# RF-Pi_Carrier_Board_v1.net
KiCad netlist of a schematic drawn in Altium Designer
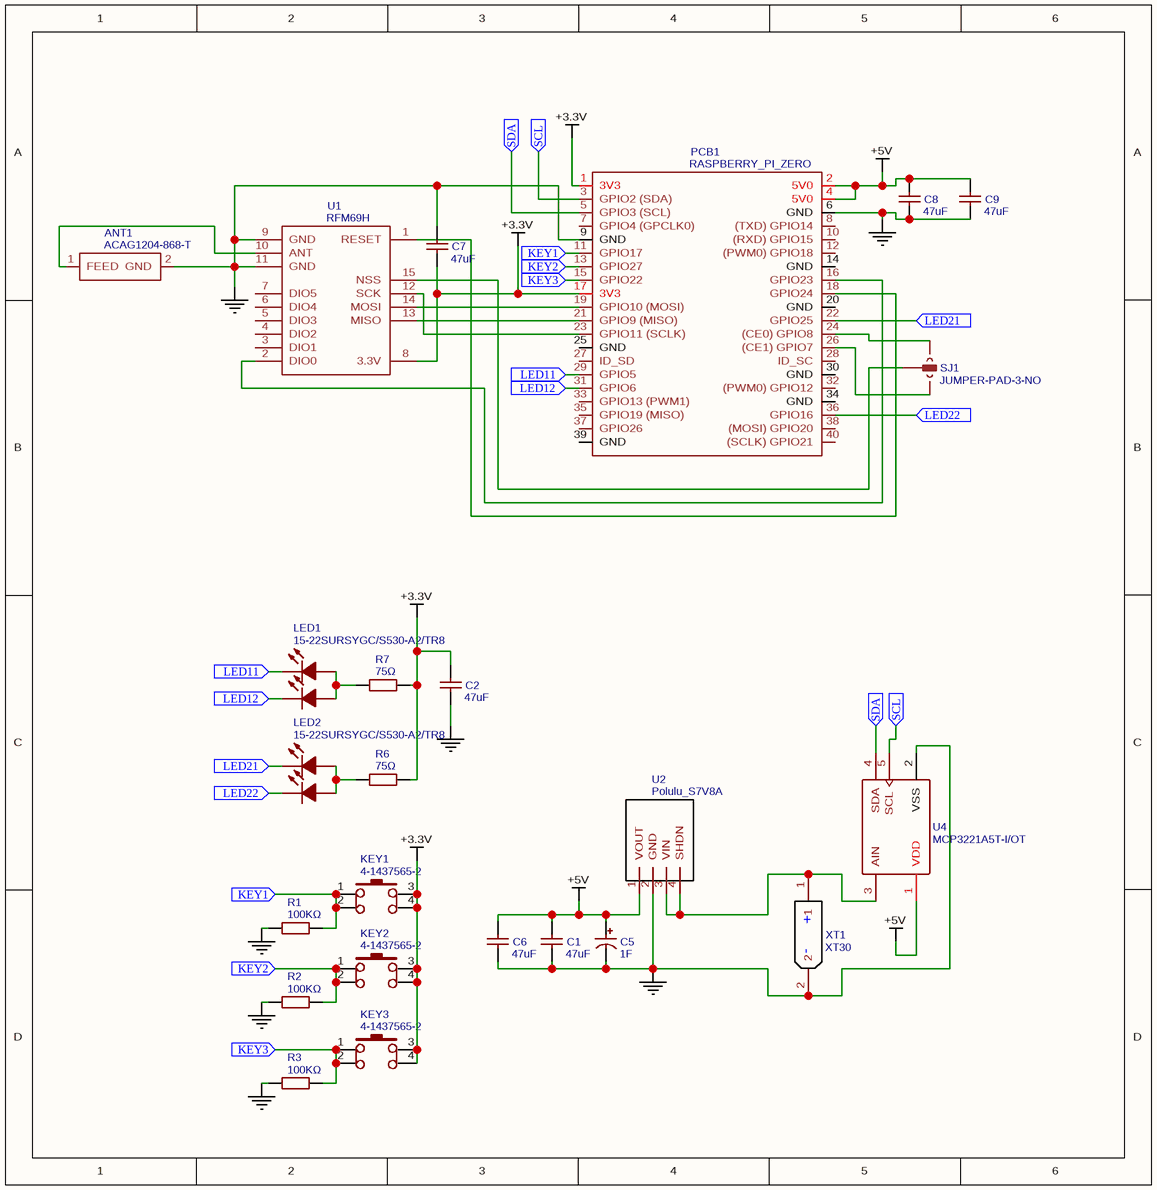
[diagram p0: RF-Pi+Carrier+Board+v1.schdoc]

(export (version "E")
  (design (tool "Eeschema 10.0.6"))
  (components
    (comp (ref "ANT1")
      (value "ACAG1204-868-T")
      (description "868 Ceramic Chip Antenna")
      (fields (field (name "CONTRIBUTOR") "JUehV"))
      (libsource (lib "altium-import") (part "root_0_ACAG1204-868-T_"))
    )
    (comp (ref "C1")
      (value "47uF")
      (fields
        (field (name "BOM_MANUFACTURER PART") "1206F476M100NT")
        (field (name "BOM_SUPPLIER PART") "C30349")
      )
      (libsource (lib "altium-import") (part "root_1_47uF_"))
    )
    (comp (ref "C2")
      (value "47uF")
      (fields
        (field (name "BOM_MANUFACTURER PART") "1206F476M100NT")
        (field (name "BOM_SUPPLIER PART") "C30349")
      )
      (libsource (lib "altium-import") (part "root_1_47uF_"))
    )
    (comp (ref "C5")
      (value "1F")
      (fields
        (field (name "BOM_MANUFACTURER PART") "SE-5R5-D105VYH")
        (field (name "BOM_SUPPLIER PART") "C118887")
        (field (name "CONTRIBUTOR") "LCSC")
      )
      (libsource (lib "altium-import") (part "root_3_1F_"))
    )
    (comp (ref "C6")
      (value "47uF")
      (fields
        (field (name "BOM_MANUFACTURER PART") "1206F476M100NT")
        (field (name "BOM_SUPPLIER PART") "C30349")
      )
      (libsource (lib "altium-import") (part "root_1_47uF_"))
    )
    (comp (ref "C7")
      (value "47uF")
      (fields
        (field (name "BOM_MANUFACTURER PART") "1206F476M100NT")
        (field (name "BOM_SUPPLIER PART") "C30349")
      )
      (libsource (lib "altium-import") (part "root_1_47uF_"))
    )
    (comp (ref "C8")
      (value "47uF")
      (fields
        (field (name "BOM_MANUFACTURER PART") "1206F476M100NT")
        (field (name "BOM_SUPPLIER PART") "C30349")
      )
      (libsource (lib "altium-import") (part "root_1_47uF_"))
    )
    (comp (ref "C9")
      (value "47uF")
      (fields
        (field (name "BOM_MANUFACTURER PART") "1206F476M100NT")
        (field (name "BOM_SUPPLIER PART") "C30349")
      )
      (libsource (lib "altium-import") (part "root_1_47uF_"))
    )
    (comp (ref "KEY1")
      (value "4-1437565-2")
      (fields (field (name "BOM_SUPPLIER PART") "C86487"))
      (libsource (lib "altium-import") (part "root_0_4-1437565-2_"))
    )
    (comp (ref "KEY2")
      (value "4-1437565-2")
      (fields (field (name "BOM_SUPPLIER PART") "C86487"))
      (libsource (lib "altium-import") (part "root_0_4-1437565-2_"))
    )
    (comp (ref "KEY3")
      (value "4-1437565-2")
      (fields (field (name "BOM_SUPPLIER PART") "C86487"))
      (libsource (lib "altium-import") (part "root_0_4-1437565-2_"))
    )
    (comp (ref "LED1")
      (value "15-22SURSYGC/S530-A2/TR8")
      (fields (field (name "BOM_SUPPLIER PART") "C131251") (field (name "CONTRIBUTOR") "LCSC"))
      (libsource (lib "altium-import") (part "root_0_15-22SURSYGC/S530-A2/TR8_"))
    )
    (comp (ref "LED2")
      (value "15-22SURSYGC/S530-A2/TR8")
      (fields (field (name "BOM_SUPPLIER PART") "C131251") (field (name "CONTRIBUTOR") "LCSC"))
      (libsource (lib "altium-import") (part "root_0_15-22SURSYGC/S530-A2/TR8_"))
    )
    (comp (ref "PCB1")
      (value "RASPBERRY_PI_ZERO")
      (description "Raspberry Pi Zero")
      (fields (field (name "BOM_MANUFACTURER PART") "?"))
      (libsource (lib "altium-import") (part "root_0_RASPBERRY_PI_ZERO_"))
    )
    (comp (ref "R1")
      (value "100KΩ")
      (fields
        (field (name "BOM_MANUFACTURER PART") "1206W4J0104T5E")
        (field (name "BOM_SUPPLIER PART") "C25647")
      )
      (libsource (lib "altium-import") (part "root_0_100KΩ_"))
    )
    (comp (ref "R2")
      (value "100KΩ")
      (fields
        (field (name "BOM_MANUFACTURER PART") "1206W4J0104T5E")
        (field (name "BOM_SUPPLIER PART") "C25647")
      )
      (libsource (lib "altium-import") (part "root_0_100KΩ_"))
    )
    (comp (ref "R3")
      (value "100KΩ")
      (fields
        (field (name "BOM_MANUFACTURER PART") "1206W4J0104T5E")
        (field (name "BOM_SUPPLIER PART") "C25647")
      )
      (libsource (lib "altium-import") (part "root_0_100KΩ_"))
    )
    (comp (ref "R6")
      (value "75Ω")
      (fields
        (field (name "BOM_MANUFACTURER PART") "1206W4F750JT5E")
        (field (name "BOM_SUPPLIER PART") "C17987")
      )
      (libsource (lib "altium-import") (part "root_0_75Ω_"))
    )
    (comp (ref "R7")
      (value "75Ω")
      (fields
        (field (name "BOM_MANUFACTURER PART") "1206W4F750JT5E")
        (field (name "BOM_SUPPLIER PART") "C17987")
      )
      (libsource (lib "altium-import") (part "root_0_75Ω_"))
    )
    (comp (ref "SJ1")
      (value "JUMPER-PAD-3-NO")
      (fields (field (name "BOM_MANUFACTURER PART") "?") (field (name "CONTRIBUTOR") "SparkFun"))
      (libsource (lib "altium-import") (part "root_0_JUMPER-PAD-3-NO_"))
    )
    (comp (ref "U1")
      (value "RFM69H")
      (fields
        (field (name "BOM_MANUFACTURER PART") "?")
        (field (name "BOM_SUPPLIER PART") "https://www.pollin.de/p/funkmodul-hoperf-rfm69hcw-868-mhz-tx-rx-810307")
        (field (name "CONTRIBUTOR") "SparkFun")
      )
      (libsource (lib "altium-import") (part "root_2_RFM69H_"))
    )
    (comp (ref "U2")
      (value "Polulu_S7V8A")
      (fields
        (field (name "BOM_MANUFACTURER PART") "?")
        (field (name "BOM_SUPPLIER PART") "2118")
        (field (name "CONTRIBUTOR") "JUehV")
      )
      (libsource (lib "altium-import") (part "root_0_Polulu_S7V8A_"))
    )
    (comp (ref "U4")
      (value "MCP3221A5T-I/OT")
      (fields (field (name "BOM_SUPPLIER PART") "C36310"))
      (libsource (lib "altium-import") (part "root_1_MCP3221A5T-I/OT_"))
    )
    (comp (ref "XT1")
      (value "XT30")
      (fields (field (name "BOM_SUPPLIER PART") "C99101") (field (name "CONTRIBUTOR") "4bucks"))
      (libsource (lib "altium-import") (part "root_3_XT30_"))
    )
  )
  (nets
    (net (code "1") (name "+3.3V") (class "Default")
      (node (ref "C2") (pin "2") (pinfunction "2_2") (pintype "passive"))
      (node (ref "C7") (pin "1") (pinfunction "1_1") (pintype "passive"))
      (node (ref "KEY1") (pin "3") (pinfunction "3_3") (pintype "passive"))
      (node (ref "KEY1") (pin "4") (pinfunction "4_4") (pintype "passive"))
      (node (ref "KEY2") (pin "3") (pinfunction "3_3") (pintype "passive"))
      (node (ref "KEY2") (pin "4") (pinfunction "4_4") (pintype "passive"))
      (node (ref "KEY3") (pin "3") (pinfunction "3_3") (pintype "passive"))
      (node (ref "KEY3") (pin "4") (pinfunction "4_4") (pintype "passive"))
      (node (ref "PCB1") (pin "1") (pinfunction "3V3_1") (pintype "passive"))
      (node (ref "PCB1") (pin "17") (pinfunction "3V3_17") (pintype "passive"))
      (node (ref "R6") (pin "2") (pinfunction "2_2") (pintype "passive"))
      (node (ref "R7") (pin "2") (pinfunction "2_2") (pintype "passive"))
      (node (ref "U1") (pin "8") (pinfunction "3.3V_8") (pintype "passive"))
    )
    (net (code "2") (name "+5V") (class "Default")
      (node (ref "C1") (pin "2") (pinfunction "2_2") (pintype "passive"))
      (node (ref "C5") (pin "1") (pinfunction "1_1") (pintype "passive"))
      (node (ref "C6") (pin "2") (pinfunction "2_2") (pintype "passive"))
      (node (ref "C8") (pin "2") (pinfunction "2_2") (pintype "passive"))
      (node (ref "C9") (pin "2") (pinfunction "2_2") (pintype "passive"))
      (node (ref "PCB1") (pin "2") (pinfunction "5V0_2") (pintype "passive"))
      (node (ref "PCB1") (pin "4") (pinfunction "5V0_4") (pintype "passive"))
      (node (ref "U2") (pin "1") (pinfunction "VOUT_1") (pintype "passive"))
      (node (ref "U4") (pin "1") (pinfunction "VDD_1") (pintype "passive"))
    )
    (net (code "3") (name "/KEY1") (class "Default")
      (node (ref "KEY1") (pin "1") (pinfunction "1_1") (pintype "passive"))
      (node (ref "KEY1") (pin "2") (pinfunction "2_2") (pintype "passive"))
      (node (ref "PCB1") (pin "11") (pinfunction "GPIO17_11") (pintype "passive"))
      (node (ref "R1") (pin "2") (pinfunction "2_2") (pintype "passive"))
    )
    (net (code "4") (name "/KEY2") (class "Default")
      (node (ref "KEY2") (pin "1") (pinfunction "1_1") (pintype "passive"))
      (node (ref "KEY2") (pin "2") (pinfunction "2_2") (pintype "passive"))
      (node (ref "PCB1") (pin "13") (pinfunction "GPIO27_13") (pintype "passive"))
      (node (ref "R2") (pin "2") (pinfunction "2_2") (pintype "passive"))
    )
    (net (code "5") (name "/KEY3") (class "Default")
      (node (ref "KEY3") (pin "1") (pinfunction "1_1") (pintype "passive"))
      (node (ref "KEY3") (pin "2") (pinfunction "2_2") (pintype "passive"))
      (node (ref "PCB1") (pin "15") (pinfunction "GPIO22_15") (pintype "passive"))
      (node (ref "R3") (pin "2") (pinfunction "2_2") (pintype "passive"))
    )
    (net (code "6") (name "/LED11") (class "Default")
      (node (ref "LED1") (pin "2") (pinfunction "K_2") (pintype "passive"))
      (node (ref "PCB1") (pin "29") (pinfunction "GPIO5_29") (pintype "passive"))
    )
    (net (code "7") (name "/LED12") (class "Default")
      (node (ref "LED1") (pin "4") (pinfunction "K_4") (pintype "passive"))
      (node (ref "PCB1") (pin "31") (pinfunction "GPIO6_31") (pintype "passive"))
    )
    (net (code "8") (name "/LED21") (class "Default")
      (node (ref "LED2") (pin "2") (pinfunction "K_2") (pintype "passive"))
      (node (ref "PCB1") (pin "22") (pinfunction "GPIO25_22") (pintype "passive"))
    )
    (net (code "9") (name "/LED22") (class "Default")
      (node (ref "LED2") (pin "4") (pinfunction "K_4") (pintype "passive"))
      (node (ref "PCB1") (pin "36") (pinfunction "GPIO16_36") (pintype "passive"))
    )
    (net (code "10") (name "/SCL") (class "Default")
      (node (ref "PCB1") (pin "3") (pinfunction "GPIO2_(SDA)_3") (pintype "passive"))
      (node (ref "U4") (pin "5") (pinfunction "SCL_5") (pintype "passive"))
    )
    (net (code "11") (name "/SDA") (class "Default")
      (node (ref "PCB1") (pin "5") (pinfunction "GPIO3_(SCL)_5") (pintype "passive"))
      (node (ref "U4") (pin "4") (pinfunction "SDA_4") (pintype "passive"))
    )
    (net (code "12") (name "GND") (class "Default")
      (node (ref "ANT1") (pin "2") (pinfunction "GND_2") (pintype "passive"))
      (node (ref "C1") (pin "1") (pinfunction "1_1") (pintype "passive"))
      (node (ref "C2") (pin "1") (pinfunction "1_1") (pintype "passive"))
      (node (ref "C5") (pin "2") (pinfunction "2_2") (pintype "passive"))
      (node (ref "C6") (pin "1") (pinfunction "1_1") (pintype "passive"))
      (node (ref "C7") (pin "2") (pinfunction "2_2") (pintype "passive"))
      (node (ref "C8") (pin "1") (pinfunction "1_1") (pintype "passive"))
      (node (ref "C9") (pin "1") (pinfunction "1_1") (pintype "passive"))
      (node (ref "PCB1") (pin "6") (pinfunction "GND_6") (pintype "passive"))
      (node (ref "PCB1") (pin "9") (pinfunction "GND_9") (pintype "passive"))
      (node (ref "R1") (pin "1") (pinfunction "1_1") (pintype "passive"))
      (node (ref "R2") (pin "1") (pinfunction "1_1") (pintype "passive"))
      (node (ref "R3") (pin "1") (pinfunction "1_1") (pintype "passive"))
      (node (ref "U1") (pin "11") (pinfunction "GND_11") (pintype "passive"))
      (node (ref "U1") (pin "9") (pinfunction "GND_9") (pintype "passive"))
      (node (ref "U2") (pin "2") (pinfunction "GND_2") (pintype "passive"))
      (node (ref "U4") (pin "2") (pinfunction "VSS_2") (pintype "passive"))
      (node (ref "XT1") (pin "2") (pinfunction "2_2") (pintype "passive"))
    )
    (net (code "13") (name "Net-(ANT1-FEED)") (class "Default")
      (node (ref "ANT1") (pin "1") (pinfunction "FEED_1") (pintype "passive"))
      (node (ref "U1") (pin "10") (pinfunction "ANT_10") (pintype "passive"))
    )
    (net (code "14") (name "Net-(LED1-A-Pad1)") (class "Default")
      (node (ref "LED1") (pin "1") (pinfunction "A_1") (pintype "passive"))
      (node (ref "LED1") (pin "3") (pinfunction "A_3") (pintype "passive"))
      (node (ref "R7") (pin "1") (pinfunction "1_1") (pintype "passive"))
    )
    (net (code "15") (name "Net-(LED2-A-Pad1)") (class "Default")
      (node (ref "LED2") (pin "1") (pinfunction "A_1") (pintype "passive"))
      (node (ref "LED2") (pin "3") (pinfunction "A_3") (pintype "passive"))
      (node (ref "R6") (pin "1") (pinfunction "1_1") (pintype "passive"))
    )
    (net (code "16") (name "Net-(PCB1-(CE0)_GPIO8)") (class "Default")
      (node (ref "PCB1") (pin "24") (pinfunction "(CE0)_GPIO8_24") (pintype "passive"))
      (node (ref "SJ1") (pin "1") (pinfunction "1_1") (pintype "passive"))
    )
    (net (code "17") (name "Net-(PCB1-(CE1)_GPIO7)") (class "Default")
      (node (ref "PCB1") (pin "26") (pinfunction "(CE1)_GPIO7_26") (pintype "passive"))
      (node (ref "SJ1") (pin "3") (pinfunction "3_3") (pintype "passive"))
    )
    (net (code "18") (name "Net-(PCB1-GPIO9_(MISO))") (class "Default")
      (node (ref "PCB1") (pin "21") (pinfunction "GPIO9_(MISO)_21") (pintype "passive"))
      (node (ref "U1") (pin "13") (pinfunction "MISO_13") (pintype "passive"))
    )
    (net (code "19") (name "Net-(PCB1-GPIO10_(MOSI))") (class "Default")
      (node (ref "PCB1") (pin "19") (pinfunction "GPIO10_(MOSI)_19") (pintype "passive"))
      (node (ref "U1") (pin "14") (pinfunction "MOSI_14") (pintype "passive"))
    )
    (net (code "20") (name "Net-(PCB1-GPIO11_(SCLK))") (class "Default")
      (node (ref "PCB1") (pin "23") (pinfunction "GPIO11_(SCLK)_23") (pintype "passive"))
      (node (ref "U1") (pin "12") (pinfunction "SCK_12") (pintype "passive"))
    )
    (net (code "21") (name "Net-(PCB1-GPIO23)") (class "Default")
      (node (ref "PCB1") (pin "16") (pinfunction "GPIO23_16") (pintype "passive"))
      (node (ref "U1") (pin "2") (pinfunction "DIO0_2") (pintype "passive"))
    )
    (net (code "22") (name "Net-(PCB1-GPIO24)") (class "Default")
      (node (ref "PCB1") (pin "18") (pinfunction "GPIO24_18") (pintype "passive"))
      (node (ref "U1") (pin "1") (pinfunction "RESET_1") (pintype "passive"))
    )
    (net (code "23") (name "Net-(U1-NSS)") (class "Default")
      (node (ref "SJ1") (pin "2") (pinfunction "2_2") (pintype "passive"))
      (node (ref "U1") (pin "15") (pinfunction "NSS_15") (pintype "passive"))
    )
    (net (code "24") (name "Net-(U2-SHDN)") (class "Default")
      (node (ref "U2") (pin "3") (pinfunction "VIN_3") (pintype "passive"))
      (node (ref "U2") (pin "4") (pinfunction "SHDN_4") (pintype "passive"))
      (node (ref "U4") (pin "3") (pinfunction "AIN_3") (pintype "passive"))
      (node (ref "XT1") (pin "1") (pinfunction "1_1") (pintype "passive"))
    )
    (net (code "25") (name "unconnected-(PCB1-(MOSI)_GPIO20-Pad38)") (class "Default")
      (node (ref "PCB1") (pin "38") (pinfunction "(MOSI)_GPIO20_38") (pintype "passive"))
    )
    (net (code "26") (name "unconnected-(PCB1-(PWM0)_GPIO12-Pad32)") (class "Default")
      (node (ref "PCB1") (pin "32") (pinfunction "(PWM0)_GPIO12_32") (pintype "passive"))
    )
    (net (code "27") (name "unconnected-(PCB1-(PWM0)_GPIO18-Pad12)") (class "Default")
      (node (ref "PCB1") (pin "12") (pinfunction "(PWM0)_GPIO18_12") (pintype "passive"))
    )
    (net (code "28") (name "unconnected-(PCB1-(RXD)_GPIO15-Pad10)") (class "Default")
      (node (ref "PCB1") (pin "10") (pinfunction "(RXD)_GPIO15_10") (pintype "passive"))
    )
    (net (code "29") (name "unconnected-(PCB1-(SCLK)_GPIO21-Pad40)") (class "Default")
      (node (ref "PCB1") (pin "40") (pinfunction "(SCLK)_GPIO21_40") (pintype "passive"))
    )
    (net (code "30") (name "unconnected-(PCB1-(TXD)_GPIO14-Pad8)") (class "Default")
      (node (ref "PCB1") (pin "8") (pinfunction "(TXD)_GPIO14_8") (pintype "passive"))
    )
    (net (code "31") (name "unconnected-(PCB1-GND-Pad14)") (class "Default")
      (node (ref "PCB1") (pin "14") (pinfunction "GND_14") (pintype "passive"))
    )
    (net (code "32") (name "unconnected-(PCB1-GND-Pad20)") (class "Default")
      (node (ref "PCB1") (pin "20") (pinfunction "GND_20") (pintype "passive"))
    )
    (net (code "33") (name "unconnected-(PCB1-GND-Pad25)") (class "Default")
      (node (ref "PCB1") (pin "25") (pinfunction "GND_25") (pintype "passive"))
    )
    (net (code "34") (name "unconnected-(PCB1-GND-Pad30)") (class "Default")
      (node (ref "PCB1") (pin "30") (pinfunction "GND_30") (pintype "passive"))
    )
    (net (code "35") (name "unconnected-(PCB1-GND-Pad34)") (class "Default")
      (node (ref "PCB1") (pin "34") (pinfunction "GND_34") (pintype "passive"))
    )
    (net (code "36") (name "unconnected-(PCB1-GND-Pad39)") (class "Default")
      (node (ref "PCB1") (pin "39") (pinfunction "GND_39") (pintype "passive"))
    )
    (net (code "37") (name "unconnected-(PCB1-GPIO4_(GPCLK0)-Pad7)") (class "Default")
      (node (ref "PCB1") (pin "7") (pinfunction "GPIO4_(GPCLK0)_7") (pintype "passive"))
    )
    (net (code "38") (name "unconnected-(PCB1-GPIO13_(PWM1)-Pad33)") (class "Default")
      (node (ref "PCB1") (pin "33") (pinfunction "GPIO13_(PWM1)_33") (pintype "passive"))
    )
    (net (code "39") (name "unconnected-(PCB1-GPIO19_(MISO)-Pad35)") (class "Default")
      (node (ref "PCB1") (pin "35") (pinfunction "GPIO19_(MISO)_35") (pintype "passive"))
    )
    (net (code "40") (name "unconnected-(PCB1-GPIO26-Pad37)") (class "Default")
      (node (ref "PCB1") (pin "37") (pinfunction "GPIO26_37") (pintype "passive"))
    )
    (net (code "41") (name "unconnected-(PCB1-ID_SC-Pad28)") (class "Default")
      (node (ref "PCB1") (pin "28") (pinfunction "ID_SC_28") (pintype "passive"))
    )
    (net (code "42") (name "unconnected-(PCB1-ID_SD-Pad27)") (class "Default")
      (node (ref "PCB1") (pin "27") (pinfunction "ID_SD_27") (pintype "passive"))
    )
    (net (code "43") (name "unconnected-(U1-DIO1-Pad3)") (class "Default")
      (node (ref "U1") (pin "3") (pinfunction "DIO1_3") (pintype "passive"))
    )
    (net (code "44") (name "unconnected-(U1-DIO2-Pad4)") (class "Default")
      (node (ref "U1") (pin "4") (pinfunction "DIO2_4") (pintype "passive"))
    )
    (net (code "45") (name "unconnected-(U1-DIO3-Pad5)") (class "Default")
      (node (ref "U1") (pin "5") (pinfunction "DIO3_5") (pintype "passive"))
    )
    (net (code "46") (name "unconnected-(U1-DIO4-Pad6)") (class "Default")
      (node (ref "U1") (pin "6") (pinfunction "DIO4_6") (pintype "passive"))
    )
    (net (code "47") (name "unconnected-(U1-DIO5-Pad7)") (class "Default")
      (node (ref "U1") (pin "7") (pinfunction "DIO5_7") (pintype "passive"))
    )
  )
)
